# RELAY2.net
KiCad netlist of a schematic drawn in Altium Designer
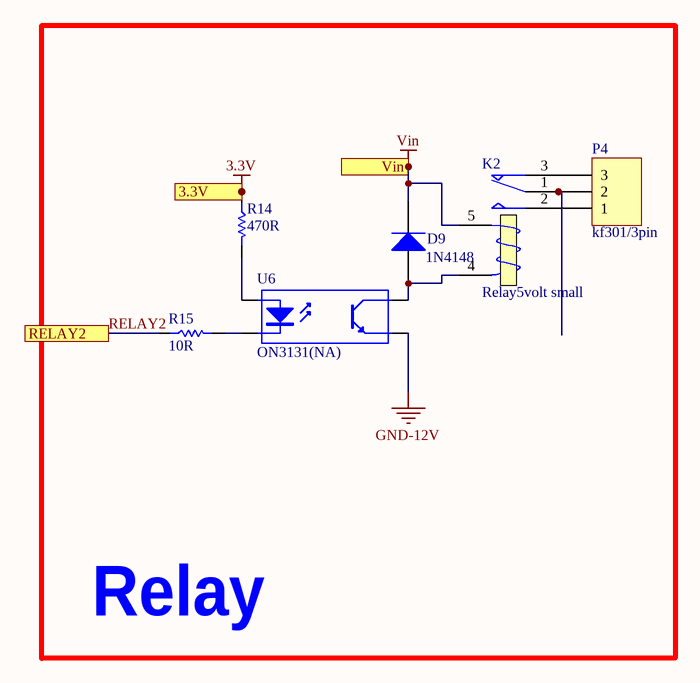
[diagram p0: RELAY2.SchDoc]

(export (version "E")
  (design (tool "Eeschema 10.0.6"))
  (components
    (comp (ref "D9")
      (value "1N4148")
      (footprint "sod123")
      (description "1 Amp General Purpose Rectifier")
      (fields (field (name "PUBLISHER") "Altium Limited"))
      (libsource (lib "Miscellaneous Devices") (part "Diode 1N4007"))
    )
    (comp (ref "K2")
      (value "Relay5volt small")
      (footprint "relay5_childern")
      (description "SPDT Relay")
      (fields (field (name "PUBLISHER") "Altium Limited"))
      (libsource (lib "FLIB") (part "Relay"))
    )
    (comp (ref "P4")
      (value "kf301/3pin")
      (footprint "Blue Connector 1*3 -kf301")
      (fields (field (name "PUBLISHER") "Altium Limited"))
      (libsource (lib "Miscellaneous Connectors") (part "Header 3"))
    )
    (comp (ref "R14")
      (value "470R")
      (footprint "0805/resistor")
      (description "Resistor")
      (fields (field (name "TOLERANCE") "5%") (field (name "POWER") "1/8 W"))
      (libsource (lib "skille") (part "Resistor"))
    )
    (comp (ref "R15")
      (value "10R")
      (footprint "0805/resistor")
      (description "Resistor")
      (fields (field (name "TOLERANCE") "5%") (field (name "POWER") "1/8 W"))
      (libsource (lib "skille") (part "Resistor"))
    )
    (comp (ref "U6")
      (value "ON3131(NA)")
      (footprint "OPTO_COUPLER")
      (description "4-Pin Phototransistor Optocoupler")
      (fields (field (name "PUBLISHER") "Altium Limited"))
      (libsource (lib "skille") (part "Optoisolator1"))
    )
  )
  (nets
    (net (code "1") (name "/RELAY2") (class "Default")
      (node (ref "R15") (pin "1") (pinfunction "1_1") (pintype "passive"))
    )
    (net (code "2") (name "3.3V") (class "Default")
      (node (ref "R14") (pin "1") (pinfunction "1_1") (pintype "passive"))
    )
    (net (code "3") (name "GND-12V") (class "Default")
      (node (ref "U6") (pin "3") (pinfunction "E_3") (pintype "passive"))
    )
    (net (code "4") (name "Net-(K2-COM)") (class "Default")
      (node (ref "K2") (pin "1") (pinfunction "COM_1") (pintype "passive"))
      (node (ref "P4") (pin "2") (pinfunction "2_2") (pintype "passive"))
    )
    (net (code "5") (name "Net-(K2-NO)") (class "Default")
      (node (ref "K2") (pin "2") (pinfunction "NO_2") (pintype "passive"))
      (node (ref "P4") (pin "1") (pinfunction "1_1") (pintype "passive"))
    )
    (net (code "6") (name "Net-(K2-T1)") (class "Default")
      (node (ref "K2") (pin "3") (pinfunction "T1_3") (pintype "passive"))
      (node (ref "P4") (pin "3") (pinfunction "3_3") (pintype "passive"))
    )
    (net (code "7") (name "Net-(K2-T2)") (class "Default")
      (node (ref "D9") (pin "A") (pinfunction "A_A") (pintype "passive"))
      (node (ref "K2") (pin "4") (pinfunction "T2_4") (pintype "passive"))
      (node (ref "U6") (pin "4") (pinfunction "C_4") (pintype "passive"))
    )
    (net (code "8") (name "Net-(U6-A)") (class "Default")
      (node (ref "R14") (pin "2") (pinfunction "2_2") (pintype "passive"))
      (node (ref "U6") (pin "1") (pinfunction "A_1") (pintype "passive"))
    )
    (net (code "9") (name "Net-(U6-K)") (class "Default")
      (node (ref "R15") (pin "2") (pinfunction "2_2") (pintype "passive"))
      (node (ref "U6") (pin "2") (pinfunction "K_2") (pintype "passive"))
    )
    (net (code "10") (name "Vin") (class "Default")
      (node (ref "D9") (pin "K") (pinfunction "K_K") (pintype "passive"))
      (node (ref "K2") (pin "5") (pinfunction "5_5") (pintype "passive"))
    )
  )
)
